# connectors.net
KiCad netlist of a schematic drawn in Altium Designer
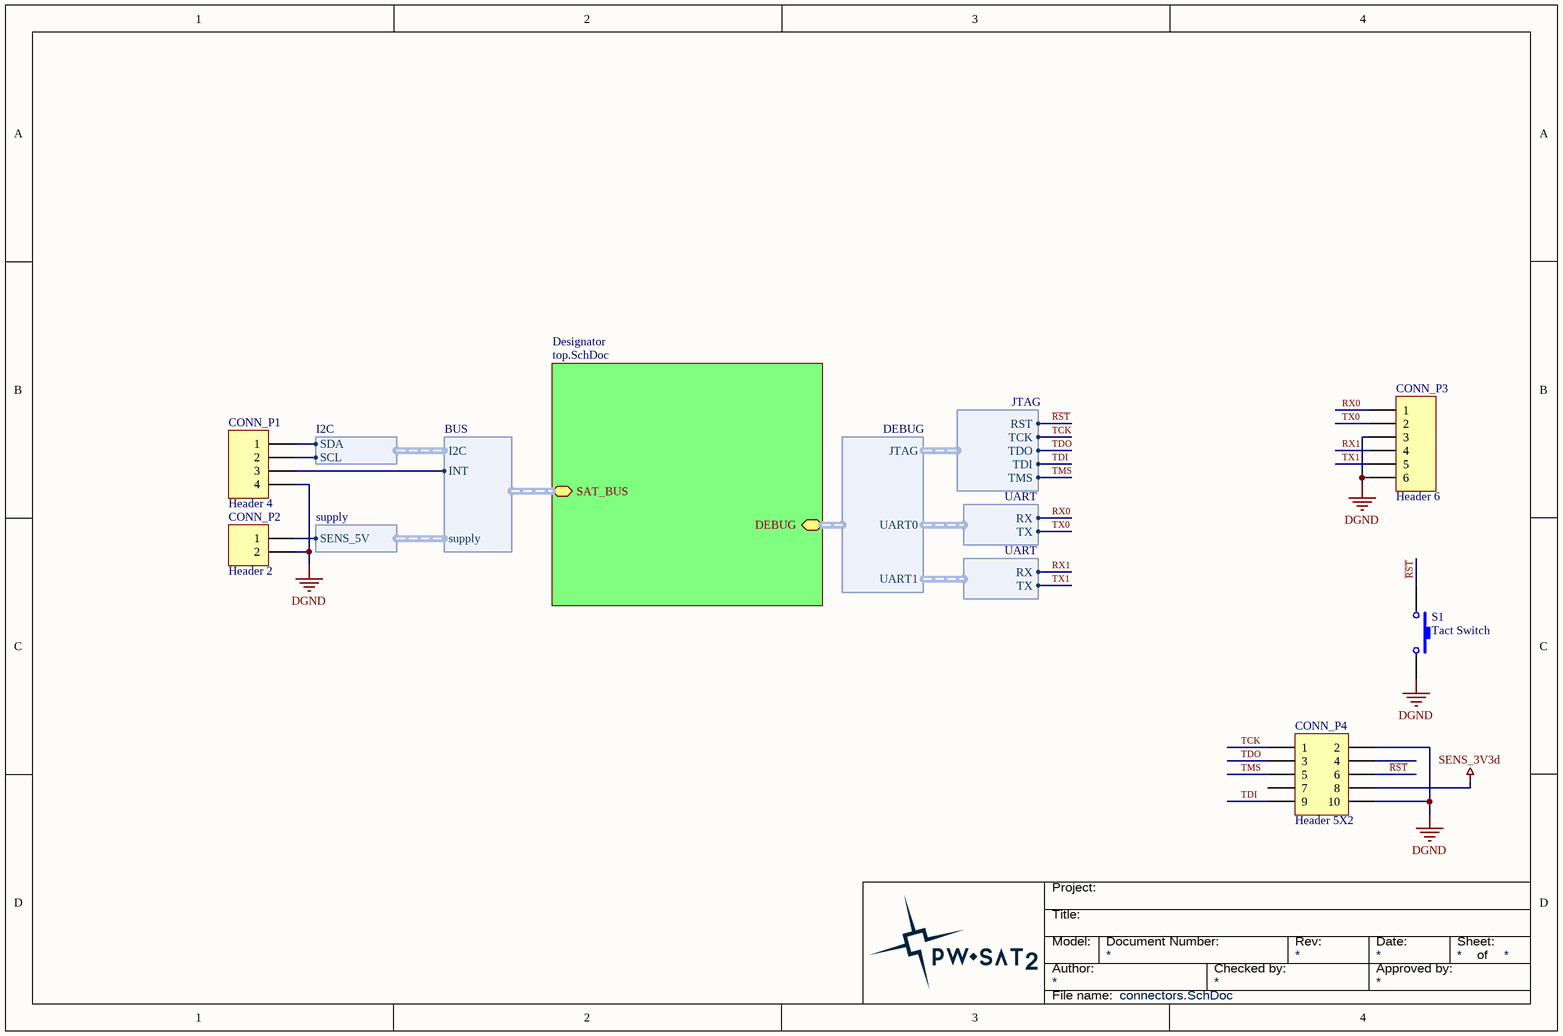
[diagram p0: connectors.SchDoc]

(export (version "E")
  (design (tool "Eeschema 10.0.6"))
  (components
    (comp (ref "CONN_P1")
      (value "Header 4")
      (footprint "HEADER 1x4 MALE")
      (description "Header, 4-Pin")
      (fields (field (name "PUBLISHER") "Altium Limited"))
      (libsource (lib "connectors_printed-circuit-board") (part "Header 4"))
    )
    (comp (ref "CONN_P2")
      (value "Header 2")
      (footprint "HEADER 1X2 Male")
      (description "Header, 2-Pin")
      (fields (field (name "PUBLISHER") "Altium Limited"))
      (libsource (lib "connectors_printed-circuit-board") (part "Header 2"))
    )
    (comp (ref "CONN_P3")
      (value "Header 6")
      (footprint "HEADER 1X6 MALE")
      (description "Header, 6-Pin")
      (fields (field (name "PUBLISHER") "Altium Limited"))
      (libsource (lib "connectors_printed-circuit-board") (part "Header 6"))
    )
    (comp (ref "CONN_P4")
      (value "Header 5X2")
      (footprint "HEADER 2X5 MALE")
      (description "Header, 5-Pin, Dual row")
      (libsource (lib "connectors_printed-circuit-board") (part "Header 5X2"))
    )
    (comp (ref "S1")
      (value "Tact Switch")
      (footprint "Tact Switch 3x6")
      (libsource (lib "switches") (part "TactSwitch"))
    )
  )
  (nets
    (net (code "8") (name "/INT") (class "Default")
      (node (ref "CONN_P1") (pin "3") (pinfunction "3_3") (pintype "passive"))
    )
    (net (code "9") (name "/RX0") (class "Default")
      (node (ref "CONN_P3") (pin "1") (pinfunction "1_1") (pintype "passive"))
    )
    (net (code "10") (name "/RX1") (class "Default")
      (node (ref "CONN_P3") (pin "4") (pinfunction "4_4") (pintype "passive"))
    )
    (net (code "11") (name "/SCL") (class "Default")
      (node (ref "CONN_P1") (pin "2") (pinfunction "2_2") (pintype "passive"))
    )
    (net (code "12") (name "/SDA") (class "Default")
      (node (ref "CONN_P1") (pin "1") (pinfunction "1_1") (pintype "passive"))
    )
    (net (code "13") (name "/SENS_5V") (class "Default")
      (node (ref "CONN_P2") (pin "1") (pinfunction "1_1") (pintype "passive"))
    )
    (net (code "14") (name "/TCK") (class "Default")
      (node (ref "CONN_P4") (pin "1") (pinfunction "1_1") (pintype "passive"))
    )
    (net (code "15") (name "/TDI") (class "Default")
      (node (ref "CONN_P4") (pin "9") (pinfunction "9_9") (pintype "passive"))
    )
    (net (code "16") (name "/TDO") (class "Default")
      (node (ref "CONN_P4") (pin "3") (pinfunction "3_3") (pintype "passive"))
    )
    (net (code "17") (name "/TMS") (class "Default")
      (node (ref "CONN_P4") (pin "5") (pinfunction "5_5") (pintype "passive"))
    )
    (net (code "18") (name "/TX0") (class "Default")
      (node (ref "CONN_P3") (pin "2") (pinfunction "2_2") (pintype "passive"))
    )
    (net (code "19") (name "/TX1") (class "Default")
      (node (ref "CONN_P3") (pin "5") (pinfunction "5_5") (pintype "passive"))
    )
    (net (code "26") (name "/~{RST}") (class "Default")
      (node (ref "CONN_P4") (pin "6") (pinfunction "6_6") (pintype "passive"))
      (node (ref "S1") (pin "1") (pinfunction "1_1") (pintype "passive"))
    )
    (net (code "27") (name "DGND") (class "Default")
      (node (ref "CONN_P1") (pin "4") (pinfunction "4_4") (pintype "passive"))
      (node (ref "CONN_P2") (pin "2") (pinfunction "2_2") (pintype "passive"))
      (node (ref "CONN_P3") (pin "3") (pinfunction "3_3") (pintype "passive"))
      (node (ref "CONN_P3") (pin "6") (pinfunction "6_6") (pintype "passive"))
      (node (ref "CONN_P4") (pin "10") (pinfunction "10_10") (pintype "passive"))
      (node (ref "CONN_P4") (pin "2") (pinfunction "2_2") (pintype "passive"))
      (node (ref "S1") (pin "2") (pinfunction "2_2") (pintype "passive"))
    )
    (net (code "28") (name "SENS_3V3d") (class "Default")
      (node (ref "CONN_P4") (pin "8") (pinfunction "8_8") (pintype "passive"))
    )
    (net (code "29") (name "unconnected-(CONN_P4-Pad4)") (class "Default")
      (node (ref "CONN_P4") (pin "4") (pinfunction "4_4") (pintype "passive"))
    )
    (net (code "30") (name "unconnected-(CONN_P4-Pad7)") (class "Default")
      (node (ref "CONN_P4") (pin "7") (pinfunction "7_7") (pintype "passive"))
    )
  )
)
